# POWER.net
KiCad netlist of a schematic drawn in Altium Designer
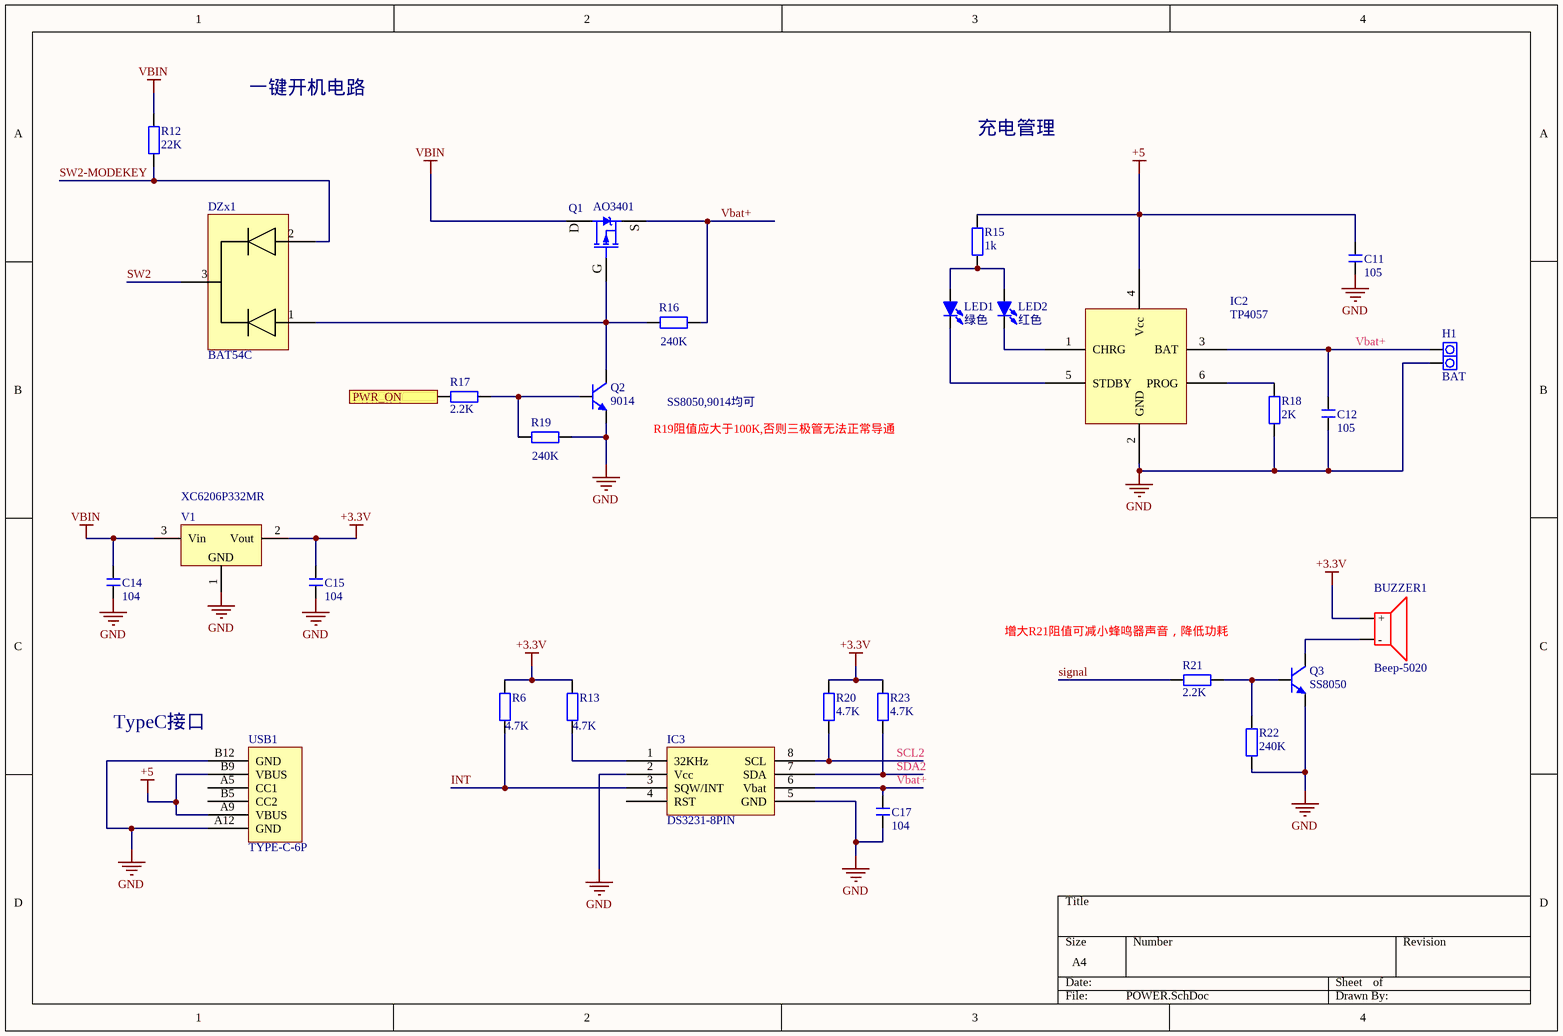
[diagram p0: POWER.SchDoc]

(export (version "E")
  (design (tool "Eeschema 10.0.6"))
  (components
    (comp (ref "BUZZER1")
      (value "Beep-5020")
      (footprint "5020BUZZER")
      (description "贴片蜂鸣器5020最小封装")
      (libsource (lib "我的元件") (part "Beep-5020"))
    )
    (comp (ref "C11")
      (value "105")
      (footprint "C0603")
      (description "无极性贴片电容")
      (fields (field (name "版权归属") "源创客"))
      (libsource (lib "3.1   - 电阻-电容-电感") (part "C"))
    )
    (comp (ref "C12")
      (value "105")
      (footprint "C0603")
      (description "无极性贴片电容")
      (fields (field (name "版权归属") "源创客"))
      (libsource (lib "3.1   - 电阻-电容-电感") (part "C"))
    )
    (comp (ref "C14")
      (value "104")
      (footprint "C0805")
      (description "无极性贴片电容")
      (fields (field (name "版权归属") "源创客"))
      (libsource (lib "3.1   - 电阻-电容-电感") (part "C"))
    )
    (comp (ref "C15")
      (value "104")
      (footprint "C0805")
      (description "无极性贴片电容")
      (fields (field (name "版权归属") "源创客"))
      (libsource (lib "3.1   - 电阻-电容-电感") (part "C"))
    )
    (comp (ref "C17")
      (value "104")
      (footprint "C0805")
      (description "无极性贴片电容")
      (fields (field (name "版权归属") "源创客"))
      (libsource (lib "3.1   - 电阻-电容-电感") (part "C"))
    )
    (comp (ref "DZx1")
      (value "BAT54C")
      (footprint "SOT23-3N")
      (description "双肖特基，共阴极")
      (libsource (lib "我的元件") (part "BAT54C"))
    )
    (comp (ref "H1")
      (value "BAT")
      (footprint "PAD2-2.54")
      (description "引线焊盘")
      (fields (field (name "版权归属") "源创客"))
      (libsource (lib "15.1 - 未分类器件") (part "PAD2"))
    )
    (comp (ref "IC2")
      (value "TP4057")
      (footprint "SOT23-6N")
      (description "500mA/600mA锂电池充电管理IC")
      (libsource (lib "1.3   - 电源类芯片") (part "TP4057/4059"))
    )
    (comp (ref "IC3")
      (value "DS3231-8PIN")
      (footprint "SOP8_N")
      (libsource (lib "我的元件") (part "DS3231-8PIN"))
    )
    (comp (ref "LED1")
      (value "绿色")
      (footprint "D0603G")
      (description "贴片LED")
      (fields (field (name "版权归属") "源创客"))
      (libsource (lib "9.1   - LED") (part "LED-SMD"))
    )
    (comp (ref "LED2")
      (value "红色")
      (footprint "D0603R")
      (description "贴片LED")
      (fields (field (name "版权归属") "源创客"))
      (libsource (lib "9.1   - LED") (part "LED-SMD"))
    )
    (comp (ref "Q1")
      (value "AO3401")
      (footprint "SOT23-3N")
      (description "P沟道场效应管")
      (fields (field (name "版权归属") "源创客"))
      (libsource (lib "6.1   - 场效应管-可控硅") (part "SI2301"))
    )
    (comp (ref "Q2")
      (value "9014")
      (footprint "SOT23-3N")
      (description "低噪放大-NPN型")
      (fields (field (name "版权归属") "源创客"))
      (libsource (lib "6.2   - 三极管") (part "9014-SMD"))
    )
    (comp (ref "Q3")
      (value "SS8050")
      (footprint "SOT23-3N")
      (description "高频放大-NPN型")
      (fields (field (name "版权归属") "源创客"))
      (libsource (lib "6.2   - 三极管") (part "8050-SMD"))
    )
    (comp (ref "R6")
      (value "4.7K")
      (footprint "R0805")
      (description "贴片电阻")
      (fields (field (name "版权归属") "源创客"))
      (libsource (lib "3.1   - 电阻-电容-电感") (part "R"))
    )
    (comp (ref "R12")
      (value "22K")
      (footprint "R0603")
      (description "贴片电阻")
      (fields (field (name "版权归属") "源创客"))
      (libsource (lib "3.1   - 电阻-电容-电感") (part "R"))
    )
    (comp (ref "R13")
      (value "4.7K")
      (footprint "R0805")
      (description "贴片电阻")
      (fields (field (name "版权归属") "源创客"))
      (libsource (lib "3.1   - 电阻-电容-电感") (part "R"))
    )
    (comp (ref "R15")
      (value "1k")
      (footprint "R0603")
      (description "贴片电阻")
      (fields (field (name "版权归属") "源创客"))
      (libsource (lib "3.1   - 电阻-电容-电感") (part "R"))
    )
    (comp (ref "R16")
      (value "240K")
      (footprint "R0603")
      (description "贴片电阻")
      (fields (field (name "版权归属") "源创客"))
      (libsource (lib "3.1   - 电阻-电容-电感") (part "R"))
    )
    (comp (ref "R17")
      (value "2.2K")
      (footprint "R0603")
      (description "贴片电阻")
      (fields (field (name "版权归属") "源创客"))
      (libsource (lib "3.1   - 电阻-电容-电感") (part "R"))
    )
    (comp (ref "R18")
      (value "2K")
      (footprint "R0603")
      (description "贴片电阻")
      (fields (field (name "版权归属") "源创客"))
      (libsource (lib "3.1   - 电阻-电容-电感") (part "R"))
    )
    (comp (ref "R19")
      (value "240K")
      (footprint "R0603")
      (description "贴片电阻")
      (fields (field (name "版权归属") "源创客"))
      (libsource (lib "3.1   - 电阻-电容-电感") (part "R"))
    )
    (comp (ref "R20")
      (value "4.7K")
      (footprint "R0805")
      (description "贴片电阻")
      (fields (field (name "版权归属") "源创客"))
      (libsource (lib "3.1   - 电阻-电容-电感") (part "R"))
    )
    (comp (ref "R21")
      (value "2.2K")
      (footprint "R0603")
      (description "贴片电阻")
      (fields (field (name "版权归属") "源创客"))
      (libsource (lib "3.1   - 电阻-电容-电感") (part "R"))
    )
    (comp (ref "R22")
      (value "240K")
      (footprint "R0603")
      (description "贴片电阻")
      (fields (field (name "版权归属") "源创客"))
      (libsource (lib "3.1   - 电阻-电容-电感") (part "R"))
    )
    (comp (ref "R23")
      (value "4.7K")
      (footprint "R0805")
      (description "贴片电阻")
      (fields (field (name "版权归属") "源创客"))
      (libsource (lib "3.1   - 电阻-电容-电感") (part "R"))
    )
    (comp (ref "USB1")
      (value "TYPE-C-6P")
      (footprint "TYPE-6P-沉板")
      (description "type-c-6p-沉板")
      (fields (field (name "版权归属") "源创客"))
      (libsource (lib "我的元件") (part "TYPE-C-6P"))
    )
    (comp (ref "V1")
      (value "XC6206P332MR")
      (footprint "SOT23-3N")
      (description "低压差线性稳压芯片")
      (fields (field (name "版权归属") "源创客"))
      (libsource (lib "1.3   - 电源类芯片") (part "XC6206P332MR"))
    )
  )
  (nets
    (net (code "1") (name "+3.3V") (class "Default")
      (node (ref "BUZZER1") (pin "1") (pinfunction "+_1") (pintype "passive"))
      (node (ref "C15") (pin "2") (pinfunction "2_2") (pintype "passive"))
      (node (ref "R13") (pin "2") (pinfunction "2_2") (pintype "passive"))
      (node (ref "R20") (pin "2") (pinfunction "2_2") (pintype "passive"))
      (node (ref "R23") (pin "2") (pinfunction "2_2") (pintype "passive"))
      (node (ref "R6") (pin "2") (pinfunction "2_2") (pintype "passive"))
      (node (ref "V1") (pin "2") (pinfunction "Vout_2") (pintype "passive"))
    )
    (net (code "2") (name "+5") (class "Default")
      (node (ref "C11") (pin "2") (pinfunction "2_2") (pintype "passive"))
      (node (ref "IC2") (pin "4") (pinfunction "Vcc_4") (pintype "passive"))
      (node (ref "R15") (pin "2") (pinfunction "2_2") (pintype "passive"))
      (node (ref "USB1") (pin "A9") (pinfunction "VBUS_A9") (pintype "passive"))
      (node (ref "USB1") (pin "B9") (pinfunction "VBUS_B9") (pintype "passive"))
    )
    (net (code "3") (name "/INT") (class "Default")
      (node (ref "IC3") (pin "3") (pinfunction "SQW/INT_3") (pintype "passive"))
      (node (ref "R6") (pin "1") (pinfunction "1_1") (pintype "passive"))
    )
    (net (code "4") (name "/PWR_ON") (class "Default")
      (node (ref "R17") (pin "1") (pinfunction "1_1") (pintype "passive"))
    )
    (net (code "5") (name "/SCL2") (class "Default")
      (node (ref "IC3") (pin "8") (pinfunction "SCL_8") (pintype "passive"))
      (node (ref "R20") (pin "1") (pinfunction "1_1") (pintype "passive"))
    )
    (net (code "6") (name "/SDA2") (class "Default")
      (node (ref "IC3") (pin "7") (pinfunction "SDA_7") (pintype "passive"))
      (node (ref "R23") (pin "1") (pinfunction "1_1") (pintype "passive"))
    )
    (net (code "7") (name "/SW2") (class "Default")
      (node (ref "DZx1") (pin "3") (pinfunction "3_3") (pintype "passive"))
    )
    (net (code "8") (name "/SW2-MODEKEY") (class "Default")
      (node (ref "DZx1") (pin "2") (pinfunction "2_2") (pintype "passive"))
      (node (ref "R12") (pin "1") (pinfunction "1_1") (pintype "passive"))
    )
    (net (code "9") (name "/Vbat+") (class "Default")
      (node (ref "C12") (pin "2") (pinfunction "2_2") (pintype "passive"))
      (node (ref "C17") (pin "2") (pinfunction "2_2") (pintype "passive"))
      (node (ref "H1") (pin "1") (pinfunction "1_1") (pintype "passive"))
      (node (ref "IC2") (pin "3") (pinfunction "BAT_3") (pintype "passive"))
      (node (ref "IC3") (pin "6") (pinfunction "Vbat_6") (pintype "passive"))
      (node (ref "Q1") (pin "2") (pinfunction "S_2") (pintype "passive"))
      (node (ref "R16") (pin "2") (pinfunction "2_2") (pintype "passive"))
    )
    (net (code "10") (name "/signal") (class "Default")
      (node (ref "R21") (pin "1") (pinfunction "1_1") (pintype "passive"))
    )
    (net (code "11") (name "GND") (class "Default")
      (node (ref "C11") (pin "1") (pinfunction "1_1") (pintype "passive"))
      (node (ref "C12") (pin "1") (pinfunction "1_1") (pintype "passive"))
      (node (ref "C14") (pin "1") (pinfunction "1_1") (pintype "passive"))
      (node (ref "C15") (pin "1") (pinfunction "1_1") (pintype "passive"))
      (node (ref "C17") (pin "1") (pinfunction "1_1") (pintype "passive"))
      (node (ref "H1") (pin "2") (pinfunction "2_2") (pintype "passive"))
      (node (ref "IC2") (pin "2") (pinfunction "GND_2") (pintype "passive"))
      (node (ref "IC3") (pin "2") (pinfunction "Vcc_2") (pintype "passive"))
      (node (ref "IC3") (pin "5") (pinfunction "GND_5") (pintype "passive"))
      (node (ref "Q2") (pin "2") (pinfunction "E_2") (pintype "passive"))
      (node (ref "Q3") (pin "2") (pinfunction "E_2") (pintype "passive"))
      (node (ref "R18") (pin "1") (pinfunction "1_1") (pintype "passive"))
      (node (ref "R19") (pin "2") (pinfunction "2_2") (pintype "passive"))
      (node (ref "R22") (pin "1") (pinfunction "1_1") (pintype "passive"))
      (node (ref "USB1") (pin "A12") (pinfunction "GND_A12") (pintype "passive"))
      (node (ref "USB1") (pin "B12") (pinfunction "GND_B12") (pintype "passive"))
      (node (ref "V1") (pin "1") (pinfunction "GND_1") (pintype "passive"))
    )
    (net (code "12") (name "Net-(BUZZER1--)") (class "Default")
      (node (ref "BUZZER1") (pin "2") (pinfunction "-_2") (pintype "passive"))
      (node (ref "Q3") (pin "3") (pinfunction "C_3") (pintype "passive"))
    )
    (net (code "13") (name "Net-(IC2-CHRG)") (class "Default")
      (node (ref "IC2") (pin "1") (pinfunction "CHRG_1") (pintype "passive"))
      (node (ref "LED2") (pin "2") (pinfunction "K_2") (pintype "passive"))
    )
    (net (code "14") (name "Net-(IC2-PROG)") (class "Default")
      (node (ref "IC2") (pin "6") (pinfunction "PROG_6") (pintype "passive"))
      (node (ref "R18") (pin "2") (pinfunction "2_2") (pintype "passive"))
    )
    (net (code "15") (name "Net-(IC2-STDBY)") (class "Default")
      (node (ref "IC2") (pin "5") (pinfunction "STDBY_5") (pintype "passive"))
      (node (ref "LED1") (pin "2") (pinfunction "K_2") (pintype "passive"))
    )
    (net (code "16") (name "Net-(IC3-32KHz)") (class "Default")
      (node (ref "IC3") (pin "1") (pinfunction "32KHz_1") (pintype "passive"))
      (node (ref "R13") (pin "1") (pinfunction "1_1") (pintype "passive"))
    )
    (net (code "17") (name "Net-(LED1-A)") (class "Default")
      (node (ref "LED1") (pin "1") (pinfunction "A_1") (pintype "passive"))
      (node (ref "LED2") (pin "1") (pinfunction "A_1") (pintype "passive"))
      (node (ref "R15") (pin "1") (pinfunction "1_1") (pintype "passive"))
    )
    (net (code "18") (name "Net-(Q1-G)") (class "Default")
      (node (ref "DZx1") (pin "1") (pinfunction "1_1") (pintype "passive"))
      (node (ref "Q1") (pin "1") (pinfunction "G_1") (pintype "passive"))
      (node (ref "Q2") (pin "3") (pinfunction "C_3") (pintype "passive"))
      (node (ref "R16") (pin "1") (pinfunction "1_1") (pintype "passive"))
    )
    (net (code "19") (name "Net-(Q2-B)") (class "Default")
      (node (ref "Q2") (pin "1") (pinfunction "B_1") (pintype "passive"))
      (node (ref "R17") (pin "2") (pinfunction "2_2") (pintype "passive"))
      (node (ref "R19") (pin "1") (pinfunction "1_1") (pintype "passive"))
    )
    (net (code "20") (name "Net-(Q3-B)") (class "Default")
      (node (ref "Q3") (pin "1") (pinfunction "B_1") (pintype "passive"))
      (node (ref "R21") (pin "2") (pinfunction "2_2") (pintype "passive"))
      (node (ref "R22") (pin "2") (pinfunction "2_2") (pintype "passive"))
    )
    (net (code "21") (name "VBIN") (class "Default")
      (node (ref "C14") (pin "2") (pinfunction "2_2") (pintype "passive"))
      (node (ref "Q1") (pin "3") (pinfunction "D_3") (pintype "passive"))
      (node (ref "R12") (pin "2") (pinfunction "2_2") (pintype "passive"))
      (node (ref "V1") (pin "3") (pinfunction "Vin_3") (pintype "passive"))
    )
    (net (code "22") (name "unconnected-(IC3-RST-Pad4)") (class "Default")
      (node (ref "IC3") (pin "4") (pinfunction "RST_4") (pintype "passive"))
    )
    (net (code "23") (name "unconnected-(USB1-CC1-PadA5)") (class "Default")
      (node (ref "USB1") (pin "A5") (pinfunction "CC1_A5") (pintype "passive"))
    )
    (net (code "24") (name "unconnected-(USB1-CC2-PadB5)") (class "Default")
      (node (ref "USB1") (pin "B5") (pinfunction "CC2_B5") (pintype "passive"))
    )
  )
)
